# regu.net
KiCad netlist of a schematic drawn in Altium Designer
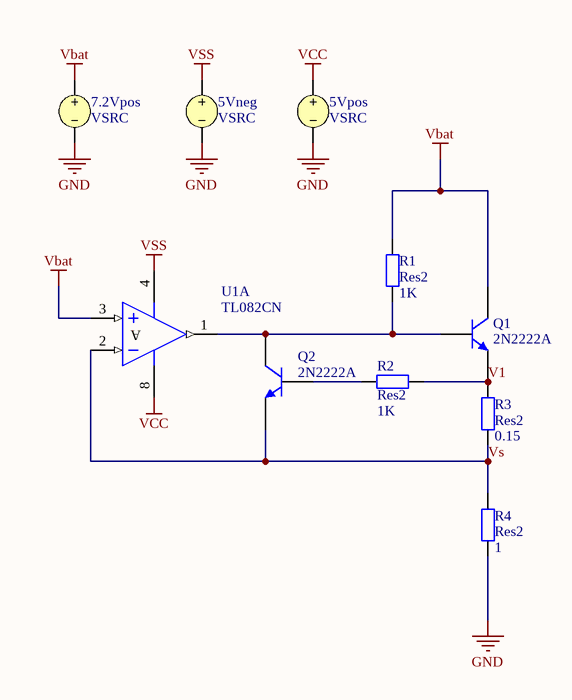
[diagram p0: regu.SchDoc]

(export (version "E")
  (design (tool "Eeschema 10.0.6"))
  (components
    (comp (ref "5Vneg")
      (value "VSRC")
      (description "Voltage Source")
      (fields (field (name "PUBLISHER") "Altium Limited"))
      (libsource (lib "Simulation Sources") (part "VSRC"))
    )
    (comp (ref "5Vpos")
      (value "VSRC")
      (description "Voltage Source")
      (fields (field (name "PUBLISHER") "Altium Limited"))
      (libsource (lib "Simulation Sources") (part "VSRC"))
    )
    (comp (ref "7.2Vpos")
      (value "VSRC")
      (description "Voltage Source")
      (fields (field (name "PUBLISHER") "Altium Limited"))
      (libsource (lib "Simulation Sources") (part "VSRC"))
    )
    (comp (ref "Q1")
      (value "2N2222A")
      (footprint "TO-18")
      (description "High Speed Switches")
      (fields (field (name "PUBLISHER") "Altium Limited"))
      (libsource (lib "LIBRAIRIE_INTEGREE_PHELMA1") (part "2N2222A"))
    )
    (comp (ref "Q2")
      (value "2N2222A")
      (footprint "TO-18")
      (description "High Speed Switches")
      (fields (field (name "PUBLISHER") "Altium Limited"))
      (libsource (lib "LIBRAIRIE_INTEGREE_PHELMA1") (part "2N2222A"))
    )
    (comp (ref "R1")
      (value "Res2")
      (footprint "res5_1/4W")
      (description "Resistor")
      (fields (field (name "ALTIUM_VALUE") "1K") (field (name "PUBLISHER") "Altium Limited"))
      (libsource (lib "LIBRAIRIE_INTEGREE_PHELMA1") (part "Res2"))
    )
    (comp (ref "R2")
      (value "Res2")
      (footprint "res5_1/4W")
      (description "Resistor")
      (fields (field (name "ALTIUM_VALUE") "1K") (field (name "PUBLISHER") "Altium Limited"))
      (libsource (lib "") (part "Res2_1"))
    )
    (comp (ref "R3")
      (value "Res2")
      (footprint "res5_1/4W")
      (description "Resistor")
      (fields (field (name "ALTIUM_VALUE") "0.15") (field (name "PUBLISHER") "Altium Limited"))
      (libsource (lib "LIBRAIRIE_INTEGREE_PHELMA1") (part "Res2"))
    )
    (comp (ref "R4")
      (value "Res2")
      (footprint "res5_1/4W")
      (description "Resistor")
      (fields (field (name "ALTIUM_VALUE") "1") (field (name "PUBLISHER") "Altium Limited"))
      (libsource (lib "LIBRAIRIE_INTEGREE_PHELMA1") (part "Res2"))
    )
    (comp (ref "U1")
      (value "TL082CN")
      (footprint "DIP8")
      (description "General-Purpose J-FET Dual Operational Amplifier")
      (fields (field (name "PUBLISHER") "Altium Limited"))
      (libsource (lib "LIBRAIRIE_INTEGREE_PHELMA1") (part "TL082CN"))
    )
  )
  (nets
    (net (code "1") (name "/V1") (class "Default")
      (node (ref "Q1") (pin "3") (pinfunction "E_3") (pintype "passive"))
      (node (ref "R2") (pin "2") (pinfunction "2_2") (pintype "passive"))
      (node (ref "R3") (pin "2") (pinfunction "2_2") (pintype "passive"))
    )
    (net (code "2") (name "/Vs") (class "Default")
      (node (ref "Q2") (pin "3") (pinfunction "E_3") (pintype "passive"))
      (node (ref "R3") (pin "1") (pinfunction "1_1") (pintype "passive"))
      (node (ref "R4") (pin "2") (pinfunction "2_2") (pintype "passive"))
      (node (ref "U1") (pin "2") (pinfunction "IN-_2") (pintype "input"))
    )
    (net (code "3") (name "GND") (class "Default")
      (node (ref "5Vneg") (pin "2") (pinfunction "2_2") (pintype "passive"))
      (node (ref "5Vpos") (pin "2") (pinfunction "2_2") (pintype "passive"))
      (node (ref "7.2Vpos") (pin "2") (pinfunction "2_2") (pintype "passive"))
      (node (ref "R4") (pin "1") (pinfunction "1_1") (pintype "passive"))
    )
    (net (code "4") (name "Net-(Q1-B)") (class "Default")
      (node (ref "Q1") (pin "1") (pinfunction "B_1") (pintype "passive"))
      (node (ref "Q2") (pin "2") (pinfunction "C_2") (pintype "passive"))
      (node (ref "R1") (pin "1") (pinfunction "1_1") (pintype "passive"))
      (node (ref "U1") (pin "1") (pinfunction "OUT_1") (pintype "output"))
    )
    (net (code "5") (name "Net-(Q2-B)") (class "Default")
      (node (ref "Q2") (pin "1") (pinfunction "B_1") (pintype "passive"))
      (node (ref "R2") (pin "1") (pinfunction "1_1") (pintype "passive"))
    )
    (net (code "6") (name "VCC") (class "Default")
      (node (ref "5Vpos") (pin "1") (pinfunction "1_1") (pintype "passive"))
      (node (ref "U1") (pin "8") (pinfunction "V+_8") (pintype "power_in"))
    )
    (net (code "7") (name "VSS") (class "Default")
      (node (ref "5Vneg") (pin "1") (pinfunction "1_1") (pintype "passive"))
      (node (ref "U1") (pin "4") (pinfunction "V-_4") (pintype "power_in"))
    )
    (net (code "8") (name "Vbat") (class "Default")
      (node (ref "7.2Vpos") (pin "1") (pinfunction "1_1") (pintype "passive"))
      (node (ref "Q1") (pin "2") (pinfunction "C_2") (pintype "passive"))
      (node (ref "R1") (pin "2") (pinfunction "2_2") (pintype "passive"))
      (node (ref "U1") (pin "3") (pinfunction "IN+_3") (pintype "input"))
    )
  )
)
